# SRAM0_-_IS61WV12816DBLL-10BLI.net
KiCad netlist of a schematic drawn in Altium Designer
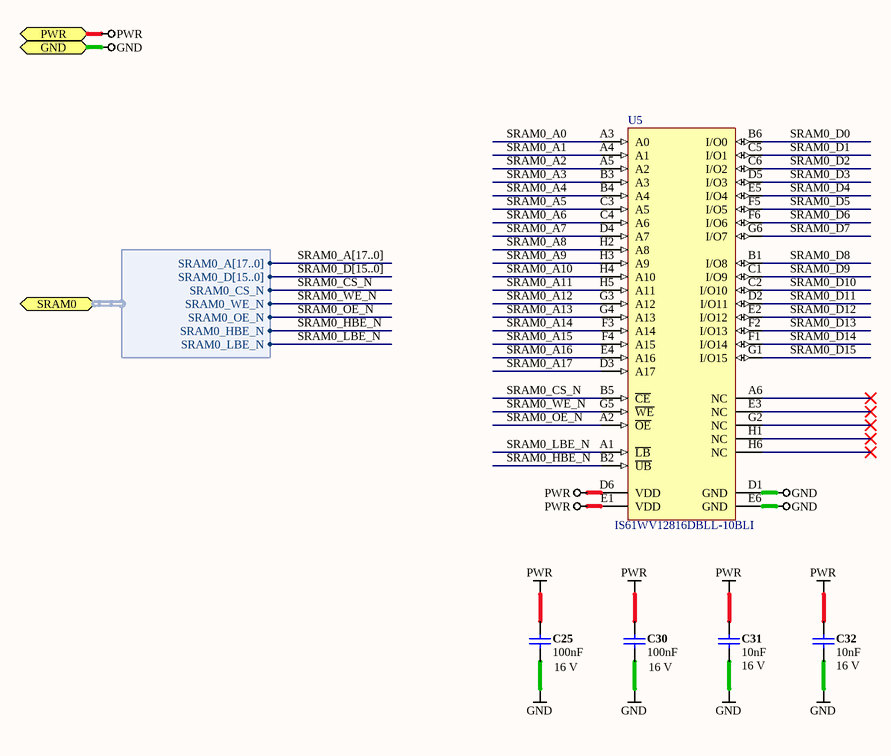
[diagram p0: SRAM0 - IS61WV12816DBLL-10BLI.SchDoc]

(export (version "E")
  (design (tool "Eeschema 10.0.6"))
  (components
    (comp (ref "C25")
      (value "100nF")
      (footprint "CAPC0402(1005)60_L")
      (fields
        (field (name "RATED VOLTAGE") "16 V")
        (field (name "TOLERANCE") "±10%")
        (field (name "Comment") "CAP 100nF 16V 0402(1005)")
      )
      (libsource (lib "Component_Database") (part "CAP_NP"))
    )
    (comp (ref "C30")
      (value "100nF")
      (footprint "CAPC0402(1005)60_L")
      (fields
        (field (name "RATED VOLTAGE") "16 V")
        (field (name "TOLERANCE") "±10%")
        (field (name "Comment") "CAP 100nF 16V 0402(1005)")
      )
      (libsource (lib "Component_Database") (part "CAP_NP"))
    )
    (comp (ref "C31")
      (value "10nF")
      (footprint "CAPC0402(1005)33_N")
      (description "CAP 10nF 16V ±10% 0402 (1005 Metric) Thickness 0.33mm SMD")
      (fields
        (field (name "TOLERANCE") "±10%")
        (field (name "RATED VOLTAGE") "16 V")
        (field (name "Comment") "CAP 10nF 16V 0402(1005)")
      )
      (libsource (lib "Altium Content Vault") (part "CMP-1034-01875-1"))
    )
    (comp (ref "C32")
      (value "10nF")
      (footprint "CAPC0402(1005)33_N")
      (description "CAP 10nF 16V ±10% 0402 (1005 Metric) Thickness 0.33mm SMD")
      (fields
        (field (name "TOLERANCE") "±10%")
        (field (name "RATED VOLTAGE") "16 V")
        (field (name "Comment") "CAP 10nF 16V 0402(1005)")
      )
      (libsource (lib "Altium Content Vault") (part "CMP-1034-01875-1"))
    )
    (comp (ref "U5")
      (value "IS61WV12816DBLL-10BLI")
      (footprint "ISSI-TF-BGA-48-6000X8000DE")
      (description "2 M High Speed Asynchronous CMOS SRAM, 128 K x 16, -40 to 85 degC, 48-Pin BGA (TF-BGA-48), Pb-Free")
      (fields (field (name "MANUFACTURER") "Integrated Silicon Solution Inc (ISSI)"))
      (libsource (lib "Altium Content Vault") (part "ISSI-IS61WV12816DALL_DBLL-TF-BGA-48"))
    )
  )
  (nets
    (net (code "2") (name "/SRAM0_A0") (class "Default")
      (node (ref "U5") (pin "A3") (pinfunction "A0_A3") (pintype "input"))
    )
    (net (code "3") (name "/SRAM0_A1") (class "Default")
      (node (ref "U5") (pin "A4") (pinfunction "A1_A4") (pintype "input"))
    )
    (net (code "4") (name "/SRAM0_A2") (class "Default")
      (node (ref "U5") (pin "A5") (pinfunction "A2_A5") (pintype "input"))
    )
    (net (code "5") (name "/SRAM0_A3") (class "Default")
      (node (ref "U5") (pin "B3") (pinfunction "A3_B3") (pintype "input"))
    )
    (net (code "6") (name "/SRAM0_A4") (class "Default")
      (node (ref "U5") (pin "B4") (pinfunction "A4_B4") (pintype "input"))
    )
    (net (code "7") (name "/SRAM0_A5") (class "Default")
      (node (ref "U5") (pin "C3") (pinfunction "A5_C3") (pintype "input"))
    )
    (net (code "8") (name "/SRAM0_A6") (class "Default")
      (node (ref "U5") (pin "C4") (pinfunction "A6_C4") (pintype "input"))
    )
    (net (code "9") (name "/SRAM0_A7") (class "Default")
      (node (ref "U5") (pin "D4") (pinfunction "A7_D4") (pintype "input"))
    )
    (net (code "10") (name "/SRAM0_A8") (class "Default")
      (node (ref "U5") (pin "H2") (pinfunction "A8_H2") (pintype "input"))
    )
    (net (code "11") (name "/SRAM0_A9") (class "Default")
      (node (ref "U5") (pin "H3") (pinfunction "A9_H3") (pintype "input"))
    )
    (net (code "12") (name "/SRAM0_A10") (class "Default")
      (node (ref "U5") (pin "H4") (pinfunction "A10_H4") (pintype "input"))
    )
    (net (code "13") (name "/SRAM0_A11") (class "Default")
      (node (ref "U5") (pin "H5") (pinfunction "A11_H5") (pintype "input"))
    )
    (net (code "14") (name "/SRAM0_A12") (class "Default")
      (node (ref "U5") (pin "G3") (pinfunction "A12_G3") (pintype "input"))
    )
    (net (code "15") (name "/SRAM0_A13") (class "Default")
      (node (ref "U5") (pin "G4") (pinfunction "A13_G4") (pintype "input"))
    )
    (net (code "16") (name "/SRAM0_A14") (class "Default")
      (node (ref "U5") (pin "F3") (pinfunction "A14_F3") (pintype "input"))
    )
    (net (code "17") (name "/SRAM0_A15") (class "Default")
      (node (ref "U5") (pin "F4") (pinfunction "A15_F4") (pintype "input"))
    )
    (net (code "18") (name "/SRAM0_A16") (class "Default")
      (node (ref "U5") (pin "E4") (pinfunction "A16_E4") (pintype "input"))
    )
    (net (code "19") (name "/SRAM0_A17") (class "Default")
      (node (ref "U5") (pin "D3") (pinfunction "A17_D3") (pintype "input"))
    )
    (net (code "21") (name "/SRAM0_CS_N") (class "Default")
      (node (ref "U5") (pin "B5") (pinfunction "~{CE}_B5") (pintype "input"))
    )
    (net (code "22") (name "/SRAM0_D0") (class "Default")
      (node (ref "U5") (pin "B6") (pinfunction "I/O0_B6") (pintype "bidirectional"))
    )
    (net (code "23") (name "/SRAM0_D1") (class "Default")
      (node (ref "U5") (pin "C5") (pinfunction "I/O1_C5") (pintype "bidirectional"))
    )
    (net (code "24") (name "/SRAM0_D2") (class "Default")
      (node (ref "U5") (pin "C6") (pinfunction "I/O2_C6") (pintype "bidirectional"))
    )
    (net (code "25") (name "/SRAM0_D3") (class "Default")
      (node (ref "U5") (pin "D5") (pinfunction "I/O3_D5") (pintype "bidirectional"))
    )
    (net (code "26") (name "/SRAM0_D4") (class "Default")
      (node (ref "U5") (pin "E5") (pinfunction "I/O4_E5") (pintype "bidirectional"))
    )
    (net (code "27") (name "/SRAM0_D5") (class "Default")
      (node (ref "U5") (pin "F5") (pinfunction "I/O5_F5") (pintype "bidirectional"))
    )
    (net (code "28") (name "/SRAM0_D6") (class "Default")
      (node (ref "U5") (pin "F6") (pinfunction "I/O6_F6") (pintype "bidirectional"))
    )
    (net (code "29") (name "/SRAM0_D7") (class "Default")
      (node (ref "U5") (pin "G6") (pinfunction "I/O7_G6") (pintype "bidirectional"))
    )
    (net (code "30") (name "/SRAM0_D8") (class "Default")
      (node (ref "U5") (pin "B1") (pinfunction "I/O8_B1") (pintype "bidirectional"))
    )
    (net (code "31") (name "/SRAM0_D9") (class "Default")
      (node (ref "U5") (pin "C1") (pinfunction "I/O9_C1") (pintype "bidirectional"))
    )
    (net (code "32") (name "/SRAM0_D10") (class "Default")
      (node (ref "U5") (pin "C2") (pinfunction "I/O10_C2") (pintype "bidirectional"))
    )
    (net (code "33") (name "/SRAM0_D11") (class "Default")
      (node (ref "U5") (pin "D2") (pinfunction "I/O11_D2") (pintype "bidirectional"))
    )
    (net (code "34") (name "/SRAM0_D12") (class "Default")
      (node (ref "U5") (pin "E2") (pinfunction "I/O12_E2") (pintype "bidirectional"))
    )
    (net (code "35") (name "/SRAM0_D13") (class "Default")
      (node (ref "U5") (pin "F2") (pinfunction "I/O13_F2") (pintype "bidirectional"))
    )
    (net (code "36") (name "/SRAM0_D14") (class "Default")
      (node (ref "U5") (pin "F1") (pinfunction "I/O14_F1") (pintype "bidirectional"))
    )
    (net (code "37") (name "/SRAM0_D15") (class "Default")
      (node (ref "U5") (pin "G1") (pinfunction "I/O15_G1") (pintype "bidirectional"))
    )
    (net (code "39") (name "/SRAM0_HBE_N") (class "Default")
      (node (ref "U5") (pin "B2") (pinfunction "~{UB}_B2") (pintype "input"))
    )
    (net (code "40") (name "/SRAM0_LBE_N") (class "Default")
      (node (ref "U5") (pin "A1") (pinfunction "~{LB}_A1") (pintype "input"))
    )
    (net (code "41") (name "/SRAM0_OE_N") (class "Default")
      (node (ref "U5") (pin "A2") (pinfunction "~{OE}_A2") (pintype "input"))
    )
    (net (code "42") (name "/SRAM0_WE_N") (class "Default")
      (node (ref "U5") (pin "G5") (pinfunction "~{WE}_G5") (pintype "input"))
    )
    (net (code "44") (name "GND") (class "Default")
      (node (ref "C25") (pin "2") (pinfunction "2_2") (pintype "passive"))
      (node (ref "C30") (pin "2") (pinfunction "2_2") (pintype "passive"))
      (node (ref "C31") (pin "2") (pinfunction "2_2") (pintype "passive"))
      (node (ref "C32") (pin "2") (pinfunction "2_2") (pintype "passive"))
      (node (ref "U5") (pin "D1") (pinfunction "GND_D1") (pintype "power_in"))
      (node (ref "U5") (pin "E6") (pinfunction "GND_E6") (pintype "power_in"))
    )
    (net (code "45") (name "PWR") (class "Default")
      (node (ref "C25") (pin "1") (pinfunction "1_1") (pintype "passive"))
      (node (ref "C30") (pin "1") (pinfunction "1_1") (pintype "passive"))
      (node (ref "C31") (pin "1") (pinfunction "1_1") (pintype "passive"))
      (node (ref "C32") (pin "1") (pinfunction "1_1") (pintype "passive"))
      (node (ref "U5") (pin "D6") (pinfunction "VDD_D6") (pintype "power_in"))
      (node (ref "U5") (pin "E1") (pinfunction "VDD_E1") (pintype "power_in"))
    )
    (net (code "46") (name "unconnected-(U5-NC-PadA6)") (class "Default")
      (node (ref "U5") (pin "A6") (pinfunction "NC_A6") (pintype "passive+no_connect"))
    )
    (net (code "47") (name "unconnected-(U5-NC-PadE3)") (class "Default")
      (node (ref "U5") (pin "E3") (pinfunction "NC_E3") (pintype "passive+no_connect"))
    )
    (net (code "48") (name "unconnected-(U5-NC-PadG2)") (class "Default")
      (node (ref "U5") (pin "G2") (pinfunction "NC_G2") (pintype "passive+no_connect"))
    )
    (net (code "49") (name "unconnected-(U5-NC-PadH1)") (class "Default")
      (node (ref "U5") (pin "H1") (pinfunction "NC_H1") (pintype "passive+no_connect"))
    )
    (net (code "50") (name "unconnected-(U5-NC-PadH6)") (class "Default")
      (node (ref "U5") (pin "H6") (pinfunction "NC_H6") (pintype "passive+no_connect"))
    )
  )
)
